# GasC.net
KiCad netlist of a schematic drawn in EAGLE
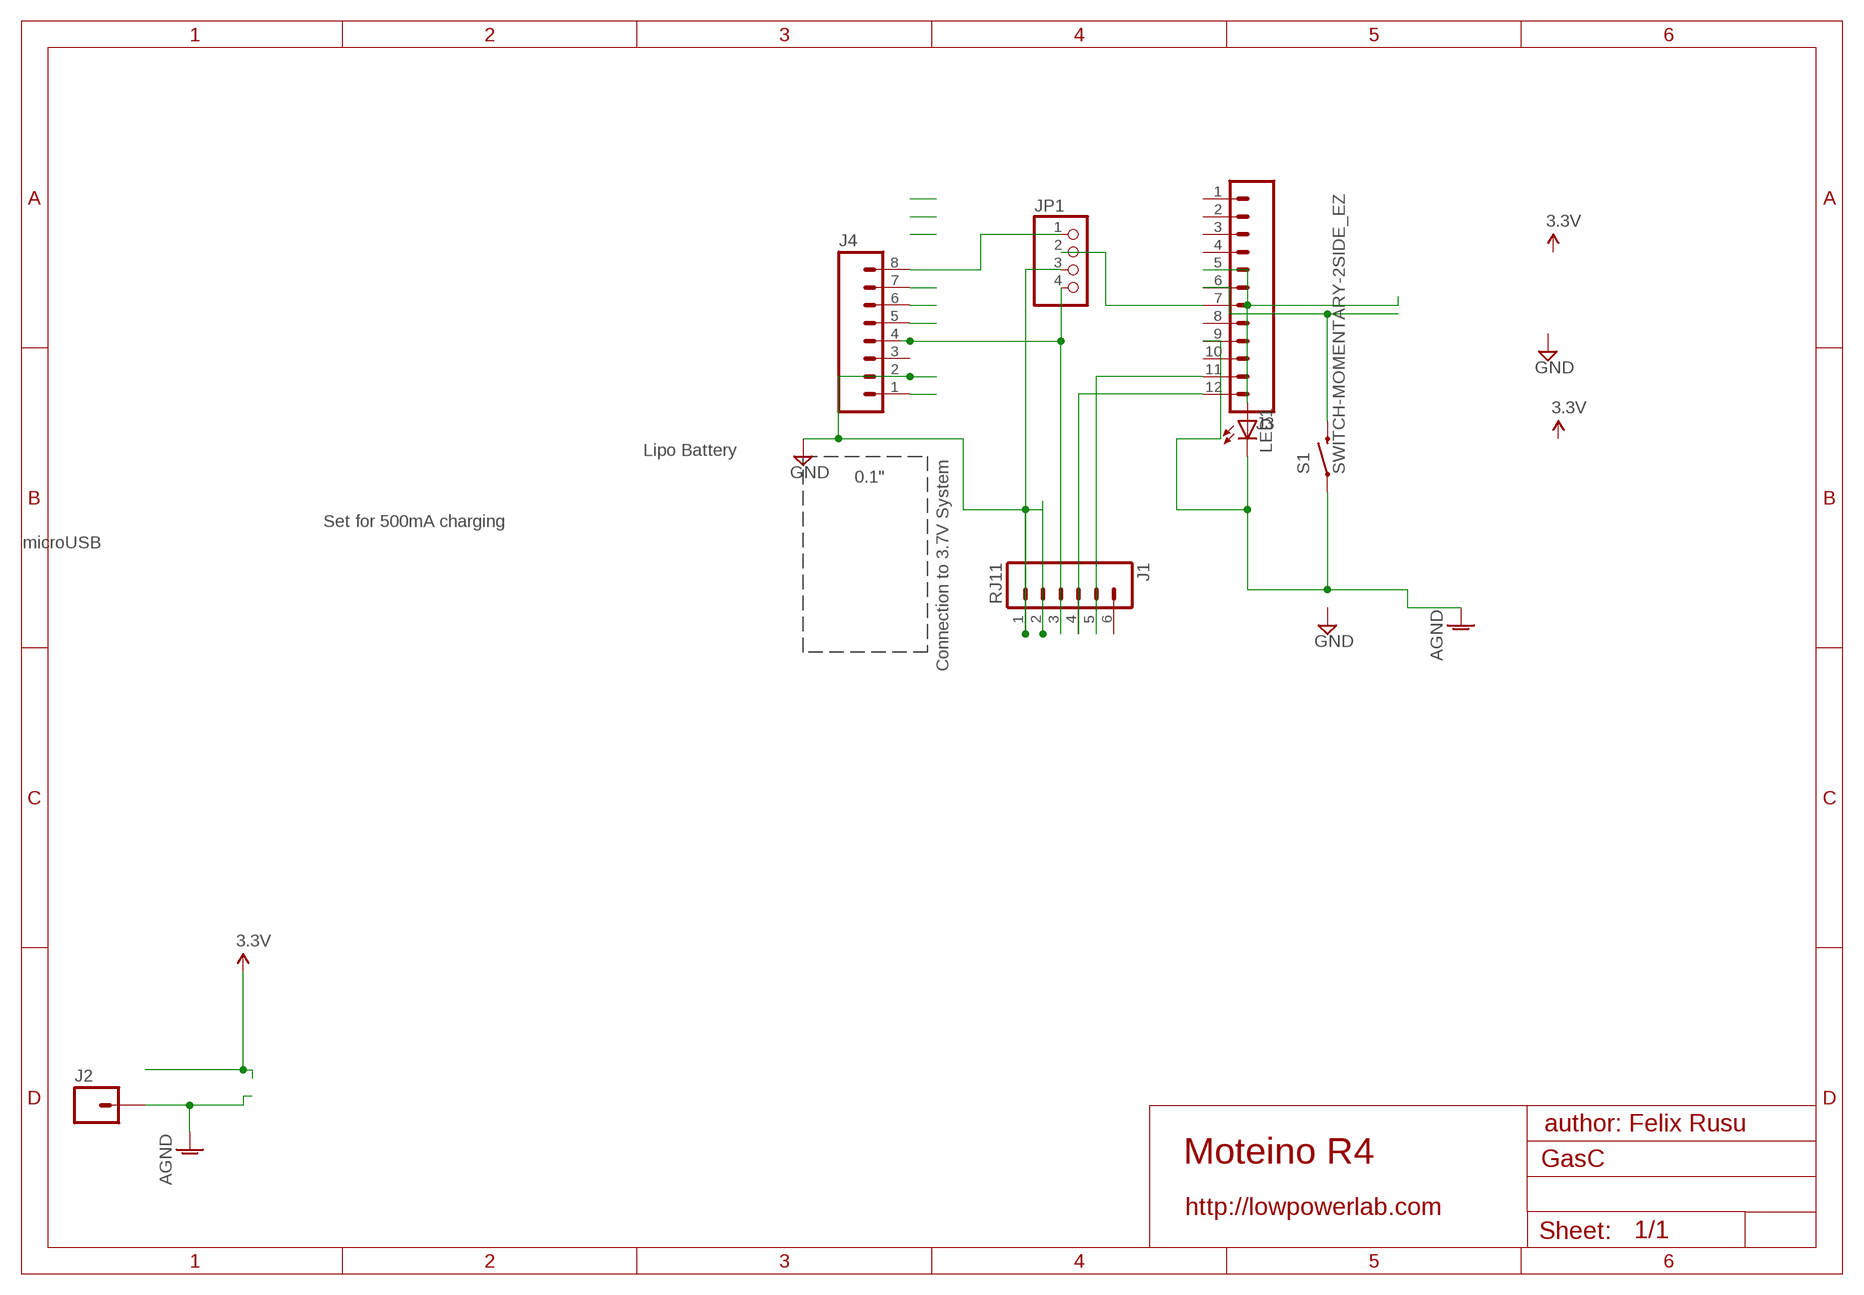
[diagram p0: schematic, sheet 1]

(export (version "E")
  (design (tool "Eeschema 10.0.6"))
  (components
    (comp (ref "J1")
      (value "RJ11")
      (footprint "eagle-import:RJ11-6")
      (libsource (lib "eagle-import") (part "RJ11-6PTH"))
    )
    (comp (ref "J2")
      (value "M01PTH")
      (footprint "eagle-import:1X01")
      (libsource (lib "eagle-import") (part "M01PTH"))
    )
    (comp (ref "J3")
      (value "M12PTH")
      (footprint "eagle-import:1X12")
      (libsource (lib "eagle-import") (part "M12PTH"))
    )
    (comp (ref "J4")
      (value "M08")
      (footprint "eagle-import:1X08_ROUND")
      (libsource (lib "eagle-import") (part "M08"))
    )
    (comp (ref "JP1")
      (value "PINHD-1X4")
      (footprint "eagle-import:1X04")
      (libsource (lib "eagle-import") (part "PINHD-1X4"))
    )
    (comp (ref "LED1")
      (value "LED3MM")
      (footprint "eagle-import:LED3MM")
      (libsource (lib "eagle-import") (part "LED3MM"))
    )
    (comp (ref "S1")
      (value "SWITCH-MOMENTARY-2SIDE_EZ")
      (footprint "eagle-import:TACTILE-PTH-SIDEEZ")
      (libsource (lib "eagle-import") (part "SWITCH-MOMENTARY-2SIDE_EZ"))
    )
  )
  (nets
    (net (code "2") (name "AGND") (class "Default")
      (node (ref "J2") (pin "1") (pinfunction "1_1") (pintype "passive"))
      (node (ref "J3") (pin "9") (pinfunction "9_9") (pintype "passive"))
      (node (ref "LED1") (pin "K") (pinfunction "C_K") (pintype "passive"))
      (node (ref "S1") (pin "1") (pinfunction "1_1") (pintype "passive"))
    )
    (net (code "3") (name "GND") (class "Default")
      (node (ref "J1") (pin "1") (pinfunction "1_1") (pintype "passive"))
      (node (ref "J1") (pin "2") (pinfunction "2_2") (pintype "passive"))
      (node (ref "J4") (pin "2") (pinfunction "2_2") (pintype "passive"))
      (node (ref "JP1") (pin "3") (pinfunction "3_3") (pintype "passive"))
    )
    (net (code "4") (name "Net-(J1-Pad3)") (class "Default")
      (node (ref "J1") (pin "3") (pinfunction "3_3") (pintype "passive"))
      (node (ref "J4") (pin "4") (pinfunction "4_4") (pintype "passive"))
      (node (ref "JP1") (pin "4") (pinfunction "4_4") (pintype "passive"))
    )
    (net (code "5") (name "Net-(J1-Pad4)") (class "Default")
      (node (ref "J1") (pin "4") (pinfunction "4_4") (pintype "passive"))
      (node (ref "J3") (pin "12") (pinfunction "12_12") (pintype "passive"))
    )
    (net (code "6") (name "Net-(J1-Pad5)") (class "Default")
      (node (ref "J1") (pin "5") (pinfunction "5_5") (pintype "passive"))
      (node (ref "J3") (pin "11") (pinfunction "11_11") (pintype "passive"))
    )
    (net (code "7") (name "Net-(J3-Pad5)") (class "Default")
      (node (ref "J3") (pin "5") (pinfunction "5_5") (pintype "passive"))
      (node (ref "LED1") (pin "A") (pinfunction "A_A") (pintype "passive"))
    )
    (net (code "8") (name "Net-(J3-Pad6)") (class "Default")
      (node (ref "J3") (pin "6") (pinfunction "6_6") (pintype "passive"))
      (node (ref "S1") (pin "2") (pinfunction "2_2") (pintype "passive"))
    )
    (net (code "9") (name "Net-(J3-Pad7)") (class "Default")
      (node (ref "J3") (pin "7") (pinfunction "7_7") (pintype "passive"))
      (node (ref "JP1") (pin "2") (pinfunction "2_2") (pintype "passive"))
    )
    (net (code "10") (name "Net-(J4-Pad8)") (class "Default")
      (node (ref "J4") (pin "8") (pinfunction "8_8") (pintype "passive"))
      (node (ref "JP1") (pin "1") (pinfunction "1_1") (pintype "passive"))
    )
    (net (code "11") (name "unconnected-(J1-Pad6)") (class "Default")
      (node (ref "J1") (pin "6") (pinfunction "6_6") (pintype "passive"))
    )
    (net (code "12") (name "unconnected-(J3-Pad1)") (class "Default")
      (node (ref "J3") (pin "1") (pinfunction "1_1") (pintype "passive"))
    )
    (net (code "13") (name "unconnected-(J3-Pad2)") (class "Default")
      (node (ref "J3") (pin "2") (pinfunction "2_2") (pintype "passive"))
    )
    (net (code "14") (name "unconnected-(J3-Pad3)") (class "Default")
      (node (ref "J3") (pin "3") (pinfunction "3_3") (pintype "passive"))
    )
    (net (code "15") (name "unconnected-(J3-Pad4)") (class "Default")
      (node (ref "J3") (pin "4") (pinfunction "4_4") (pintype "passive"))
    )
    (net (code "16") (name "unconnected-(J3-Pad8)") (class "Default")
      (node (ref "J3") (pin "8") (pinfunction "8_8") (pintype "passive"))
    )
    (net (code "17") (name "unconnected-(J3-Pad10)") (class "Default")
      (node (ref "J3") (pin "10") (pinfunction "10_10") (pintype "passive"))
    )
    (net (code "18") (name "unconnected-(J4-Pad1)") (class "Default")
      (node (ref "J4") (pin "1") (pinfunction "1_1") (pintype "passive"))
    )
    (net (code "19") (name "unconnected-(J4-Pad3)") (class "Default")
      (node (ref "J4") (pin "3") (pinfunction "3_3") (pintype "passive"))
    )
    (net (code "20") (name "unconnected-(J4-Pad5)") (class "Default")
      (node (ref "J4") (pin "5") (pinfunction "5_5") (pintype "passive"))
    )
    (net (code "21") (name "unconnected-(J4-Pad6)") (class "Default")
      (node (ref "J4") (pin "6") (pinfunction "6_6") (pintype "passive"))
    )
    (net (code "22") (name "unconnected-(J4-Pad7)") (class "Default")
      (node (ref "J4") (pin "7") (pinfunction "7_7") (pintype "passive"))
    )
  )
)
